# timetracker-1-3.net
KiCad netlist of a schematic drawn in EAGLE
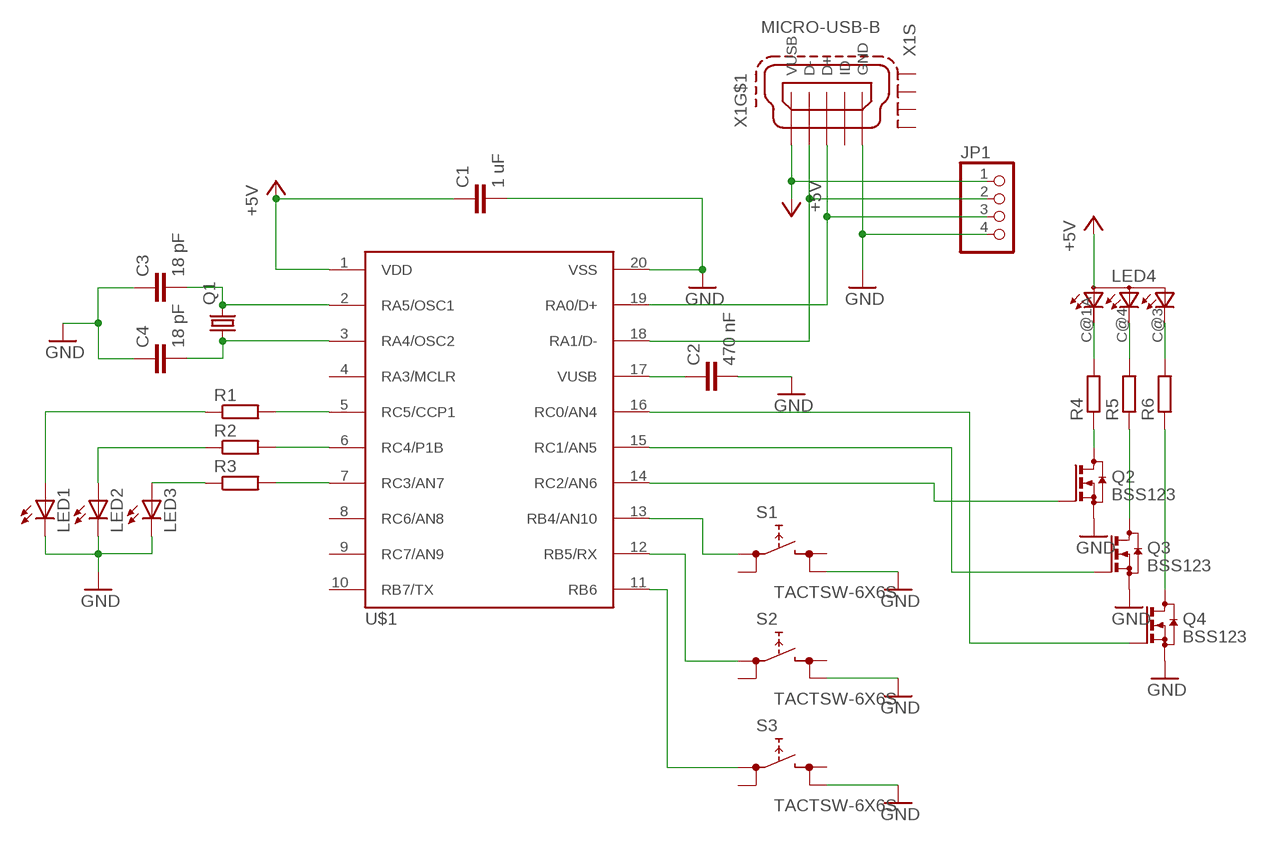
[diagram p0: schematic, sheet 1]

(export (version "E")
  (design (tool "Eeschema 10.0.6"))
  (components
    (comp (ref "C1")
      (value "1 uF")
      (footprint "eagle-import:C0805")
      (libsource (lib "eagle-import") (part "C-EUC0805"))
    )
    (comp (ref "C2")
      (value "470 nF")
      (footprint "eagle-import:C0805")
      (libsource (lib "eagle-import") (part "C-EUC0805"))
    )
    (comp (ref "C3")
      (value "18 pF")
      (footprint "eagle-import:C0805")
      (libsource (lib "eagle-import") (part "C-EUC0805"))
    )
    (comp (ref "C4")
      (value "18 pF")
      (footprint "eagle-import:C0805")
      (libsource (lib "eagle-import") (part "C-EUC0805"))
    )
    (comp (ref "JP1")
      (value "PINHD-1X4")
      (footprint "eagle-import:1X04")
      (libsource (lib "eagle-import") (part "PINHD-1X4"))
    )
    (comp (ref "LED1")
      (value "LEDSML0805")
      (footprint "eagle-import:SML0805")
      (libsource (lib "eagle-import") (part "LEDSML0805"))
    )
    (comp (ref "LED2")
      (value "LEDSML0805")
      (footprint "eagle-import:SML0805")
      (libsource (lib "eagle-import") (part "LEDSML0805"))
    )
    (comp (ref "LED3")
      (value "LEDSML0805")
      (footprint "eagle-import:SML0805")
      (libsource (lib "eagle-import") (part "LEDSML0805"))
    )
    (comp (ref "LED4")
      (value "RGBLED-3P-LCC-4")
      (footprint "eagle-import:P-LCC-4")
      (libsource (lib "eagle-import") (part "RGBLED-3P-LCC-4"))
    )
    (comp (ref "Q1")
      (value "CRYSTALHC49UP")
      (footprint "eagle-import:HC49UP")
      (libsource (lib "eagle-import") (part "CRYSTALHC49UP"))
    )
    (comp (ref "Q2")
      (value "BSS123")
      (footprint "eagle-import:SOT23")
      (libsource (lib "eagle-import") (part "BSS123"))
    )
    (comp (ref "Q3")
      (value "BSS123")
      (footprint "eagle-import:SOT23")
      (libsource (lib "eagle-import") (part "BSS123"))
    )
    (comp (ref "Q4")
      (value "BSS123")
      (footprint "eagle-import:SOT23")
      (libsource (lib "eagle-import") (part "BSS123"))
    )
    (comp (ref "R1")
      (value "R-EU_R0805")
      (footprint "eagle-import:R0805")
      (libsource (lib "eagle-import") (part "R-EU_R0805"))
    )
    (comp (ref "R2")
      (value "R-EU_R0805")
      (footprint "eagle-import:R0805")
      (libsource (lib "eagle-import") (part "R-EU_R0805"))
    )
    (comp (ref "R3")
      (value "R-EU_R0805")
      (footprint "eagle-import:R0805")
      (libsource (lib "eagle-import") (part "R-EU_R0805"))
    )
    (comp (ref "R4")
      (value "R-EU_R0805")
      (footprint "eagle-import:R0805")
      (libsource (lib "eagle-import") (part "R-EU_R0805"))
    )
    (comp (ref "R5")
      (value "R-EU_R0805")
      (footprint "eagle-import:R0805")
      (libsource (lib "eagle-import") (part "R-EU_R0805"))
    )
    (comp (ref "R6")
      (value "R-EU_R0805")
      (footprint "eagle-import:R0805")
      (libsource (lib "eagle-import") (part "R-EU_R0805"))
    )
    (comp (ref "S1")
      (value "TACTSW-6X6S")
      (footprint "eagle-import:TACTSW-6X6")
      (libsource (lib "eagle-import") (part "TACTSW-6X6S"))
    )
    (comp (ref "S2")
      (value "TACTSW-6X6S")
      (footprint "eagle-import:TACTSW-6X6")
      (libsource (lib "eagle-import") (part "TACTSW-6X6S"))
    )
    (comp (ref "S3")
      (value "TACTSW-6X6S")
      (footprint "eagle-import:TACTSW-6X6")
      (libsource (lib "eagle-import") (part "TACTSW-6X6S"))
    )
    (comp (ref "U$1")
      (value "PIC18F14K50SMD")
      (footprint "eagle-import:DIL20-SMD")
      (libsource (lib "eagle-import") (part "PIC18F14K50SMD"))
    )
    (comp (ref "X1")
      (value "MICRO-USB-B")
      (footprint "eagle-import:MICRO-B-PAC")
      (libsource (lib "eagle-import") (part "MICRO-USB-B"))
    )
  )
  (nets
    (net (code "1") (name "+5V") (class "Default")
      (node (ref "C1") (pin "1") (pinfunction "1_1") (pintype "passive"))
      (node (ref "JP1") (pin "1") (pinfunction "1_1") (pintype "passive"))
      (node (ref "LED4") (pin "A") (pinfunction "A2_A") (pintype "passive"))
      (node (ref "U$1") (pin "1") (pinfunction "VDD_1") (pintype "bidirectional"))
      (node (ref "X1") (pin "1") (pinfunction "VUSB_1") (pintype "passive"))
    )
    (net (code "2") (name "GND") (class "Default")
      (node (ref "C1") (pin "2") (pinfunction "2_2") (pintype "passive"))
      (node (ref "C2") (pin "2") (pinfunction "2_2") (pintype "passive"))
      (node (ref "C3") (pin "1") (pinfunction "1_1") (pintype "passive"))
      (node (ref "C4") (pin "1") (pinfunction "1_1") (pintype "passive"))
      (node (ref "JP1") (pin "4") (pinfunction "4_4") (pintype "passive"))
      (node (ref "LED1") (pin "C") (pinfunction "C_C") (pintype "passive"))
      (node (ref "LED2") (pin "C") (pinfunction "C_C") (pintype "passive"))
      (node (ref "LED3") (pin "C") (pinfunction "C_C") (pintype "passive"))
      (node (ref "Q2") (pin "2") (pinfunction "S_2") (pintype "passive"))
      (node (ref "Q3") (pin "2") (pinfunction "S_2") (pintype "passive"))
      (node (ref "Q4") (pin "2") (pinfunction "S_2") (pintype "passive"))
      (node (ref "S1") (pin "4") (pinfunction "2.2_4") (pintype "passive"))
      (node (ref "S2") (pin "4") (pinfunction "2.2_4") (pintype "passive"))
      (node (ref "S3") (pin "4") (pinfunction "2.2_4") (pintype "passive"))
      (node (ref "U$1") (pin "20") (pinfunction "VSS_20") (pintype "bidirectional"))
      (node (ref "X1") (pin "5") (pinfunction "GND_5") (pintype "passive"))
    )
    (net (code "3") (name "Net-(LED1-PadA)") (class "Default")
      (node (ref "LED1") (pin "A") (pinfunction "A_A") (pintype "passive"))
      (node (ref "R1") (pin "1") (pinfunction "1_1") (pintype "passive"))
    )
    (net (code "4") (name "Net-(LED2-PadA)") (class "Default")
      (node (ref "LED2") (pin "A") (pinfunction "A_A") (pintype "passive"))
      (node (ref "R2") (pin "1") (pinfunction "1_1") (pintype "passive"))
    )
    (net (code "5") (name "Net-(LED3-PadA)") (class "Default")
      (node (ref "LED3") (pin "A") (pinfunction "A_A") (pintype "passive"))
      (node (ref "R3") (pin "1") (pinfunction "1_1") (pintype "passive"))
    )
    (net (code "6") (name "Net-(LED4-CBLUE)") (class "Default")
      (node (ref "LED4") (pin "C@3") (pinfunction "CBLUE_C@3") (pintype "passive"))
      (node (ref "R6") (pin "2") (pinfunction "2_2") (pintype "passive"))
    )
    (net (code "7") (name "Net-(LED4-CGREEN)") (class "Default")
      (node (ref "LED4") (pin "C@4") (pinfunction "CGREEN_C@4") (pintype "passive"))
      (node (ref "R5") (pin "2") (pinfunction "2_2") (pintype "passive"))
    )
    (net (code "8") (name "Net-(LED4-CRED)") (class "Default")
      (node (ref "LED4") (pin "C@1") (pinfunction "CRED_C@1") (pintype "passive"))
      (node (ref "R4") (pin "2") (pinfunction "2_2") (pintype "passive"))
    )
    (net (code "9") (name "Net-(Q2-D)") (class "Default")
      (node (ref "Q2") (pin "3") (pinfunction "D_3") (pintype "passive"))
      (node (ref "R4") (pin "1") (pinfunction "1_1") (pintype "passive"))
    )
    (net (code "10") (name "Net-(Q2-G)") (class "Default")
      (node (ref "Q2") (pin "1") (pinfunction "G_1") (pintype "passive"))
      (node (ref "U$1") (pin "14") (pinfunction "RC2/AN6_14") (pintype "bidirectional"))
    )
    (net (code "11") (name "Net-(Q3-D)") (class "Default")
      (node (ref "Q3") (pin "3") (pinfunction "D_3") (pintype "passive"))
      (node (ref "R5") (pin "1") (pinfunction "1_1") (pintype "passive"))
    )
    (net (code "12") (name "Net-(Q3-G)") (class "Default")
      (node (ref "Q3") (pin "1") (pinfunction "G_1") (pintype "passive"))
      (node (ref "U$1") (pin "15") (pinfunction "RC1/AN5_15") (pintype "bidirectional"))
    )
    (net (code "13") (name "Net-(Q4-D)") (class "Default")
      (node (ref "Q4") (pin "3") (pinfunction "D_3") (pintype "passive"))
      (node (ref "R6") (pin "1") (pinfunction "1_1") (pintype "passive"))
    )
    (net (code "14") (name "Net-(Q4-G)") (class "Default")
      (node (ref "Q4") (pin "1") (pinfunction "G_1") (pintype "passive"))
      (node (ref "U$1") (pin "16") (pinfunction "RC0/AN4_16") (pintype "bidirectional"))
    )
    (net (code "15") (name "Net-(S1-1.1)") (class "Default")
      (node (ref "S1") (pin "1") (pinfunction "1.1_1") (pintype "passive"))
      (node (ref "U$1") (pin "13") (pinfunction "RB4/AN10_13") (pintype "bidirectional"))
    )
    (net (code "16") (name "Net-(S2-1.1)") (class "Default")
      (node (ref "S2") (pin "1") (pinfunction "1.1_1") (pintype "passive"))
      (node (ref "U$1") (pin "12") (pinfunction "RB5/RX_12") (pintype "bidirectional"))
    )
    (net (code "17") (name "Net-(S3-1.1)") (class "Default")
      (node (ref "S3") (pin "1") (pinfunction "1.1_1") (pintype "passive"))
      (node (ref "U$1") (pin "11") (pinfunction "RB6_11") (pintype "bidirectional"))
    )
    (net (code "18") (name "Net-(U$1-RA0{slash}D+)") (class "Default")
      (node (ref "JP1") (pin "3") (pinfunction "3_3") (pintype "passive"))
      (node (ref "U$1") (pin "19") (pinfunction "RA0/D+_19") (pintype "bidirectional"))
      (node (ref "X1") (pin "3") (pinfunction "D+_3") (pintype "passive"))
    )
    (net (code "19") (name "Net-(U$1-RA1{slash}D-)") (class "Default")
      (node (ref "JP1") (pin "2") (pinfunction "2_2") (pintype "passive"))
      (node (ref "U$1") (pin "18") (pinfunction "RA1/D-_18") (pintype "bidirectional"))
      (node (ref "X1") (pin "2") (pinfunction "D-_2") (pintype "passive"))
    )
    (net (code "20") (name "Net-(U$1-RA4{slash}OSC2)") (class "Default")
      (node (ref "C4") (pin "2") (pinfunction "2_2") (pintype "passive"))
      (node (ref "Q1") (pin "1") (pinfunction "1_1") (pintype "passive"))
      (node (ref "U$1") (pin "3") (pinfunction "RA4/OSC2_3") (pintype "bidirectional"))
    )
    (net (code "21") (name "Net-(U$1-RA5{slash}OSC1)") (class "Default")
      (node (ref "C3") (pin "2") (pinfunction "2_2") (pintype "passive"))
      (node (ref "Q1") (pin "2") (pinfunction "2_2") (pintype "passive"))
      (node (ref "U$1") (pin "2") (pinfunction "RA5/OSC1_2") (pintype "bidirectional"))
    )
    (net (code "22") (name "Net-(U$1-RC3{slash}AN7)") (class "Default")
      (node (ref "R3") (pin "2") (pinfunction "2_2") (pintype "passive"))
      (node (ref "U$1") (pin "7") (pinfunction "RC3/AN7_7") (pintype "bidirectional"))
    )
    (net (code "23") (name "Net-(U$1-RC4{slash}P1B)") (class "Default")
      (node (ref "R2") (pin "2") (pinfunction "2_2") (pintype "passive"))
      (node (ref "U$1") (pin "6") (pinfunction "RC4/P1B_6") (pintype "bidirectional"))
    )
    (net (code "24") (name "Net-(U$1-RC5{slash}CCP1)") (class "Default")
      (node (ref "R1") (pin "2") (pinfunction "2_2") (pintype "passive"))
      (node (ref "U$1") (pin "5") (pinfunction "RC5/CCP1_5") (pintype "bidirectional"))
    )
    (net (code "25") (name "Net-(U$1-VUSB)") (class "Default")
      (node (ref "C2") (pin "1") (pinfunction "1_1") (pintype "passive"))
      (node (ref "U$1") (pin "17") (pinfunction "VUSB_17") (pintype "bidirectional"))
    )
    (net (code "26") (name "unconnected-(S1-1.2-Pad2)") (class "Default")
      (node (ref "S1") (pin "2") (pinfunction "1.2_2") (pintype "passive"))
    )
    (net (code "27") (name "unconnected-(S1-2.1-Pad3)") (class "Default")
      (node (ref "S1") (pin "3") (pinfunction "2.1_3") (pintype "passive"))
    )
    (net (code "28") (name "unconnected-(S2-1.2-Pad2)") (class "Default")
      (node (ref "S2") (pin "2") (pinfunction "1.2_2") (pintype "passive"))
    )
    (net (code "29") (name "unconnected-(S2-2.1-Pad3)") (class "Default")
      (node (ref "S2") (pin "3") (pinfunction "2.1_3") (pintype "passive"))
    )
    (net (code "30") (name "unconnected-(S3-1.2-Pad2)") (class "Default")
      (node (ref "S3") (pin "2") (pinfunction "1.2_2") (pintype "passive"))
    )
    (net (code "31") (name "unconnected-(S3-2.1-Pad3)") (class "Default")
      (node (ref "S3") (pin "3") (pinfunction "2.1_3") (pintype "passive"))
    )
    (net (code "32") (name "unconnected-(U$1-RA3{slash}MCLR-Pad4)") (class "Default")
      (node (ref "U$1") (pin "4") (pinfunction "RA3/MCLR_4") (pintype "bidirectional"))
    )
    (net (code "33") (name "unconnected-(U$1-RB7{slash}TX-Pad10)") (class "Default")
      (node (ref "U$1") (pin "10") (pinfunction "RB7/TX_10") (pintype "bidirectional"))
    )
    (net (code "34") (name "unconnected-(U$1-RC6{slash}AN8-Pad8)") (class "Default")
      (node (ref "U$1") (pin "8") (pinfunction "RC6/AN8_8") (pintype "bidirectional"))
    )
    (net (code "35") (name "unconnected-(U$1-RC7{slash}AN9-Pad9)") (class "Default")
      (node (ref "U$1") (pin "9") (pinfunction "RC7/AN9_9") (pintype "bidirectional"))
    )
    (net (code "36") (name "unconnected-(X1A-ID-Pad4)") (class "Default")
      (node (ref "X1") (pin "4") (pinfunction "ID_4") (pintype "passive"))
    )
    (net (code "37") (name "unconnected-(X1B-S1-PadM1)") (class "Default")
      (node (ref "X1") (pin "M1") (pinfunction "S1_M1") (pintype "passive"))
    )
    (net (code "38") (name "unconnected-(X1B-S2-PadM2)") (class "Default")
      (node (ref "X1") (pin "M2") (pinfunction "S2_M2") (pintype "passive"))
    )
    (net (code "39") (name "unconnected-(X1B-S3-PadM3)") (class "Default")
      (node (ref "X1") (pin "M3") (pinfunction "S3_M3") (pintype "passive"))
    )
    (net (code "40") (name "unconnected-(X1B-S4-PadM4)") (class "Default")
      (node (ref "X1") (pin "M4") (pinfunction "S4_M4") (pintype "passive"))
    )
  )
)
